# DiffVer.net
KiCad netlist of a schematic drawn in EAGLE
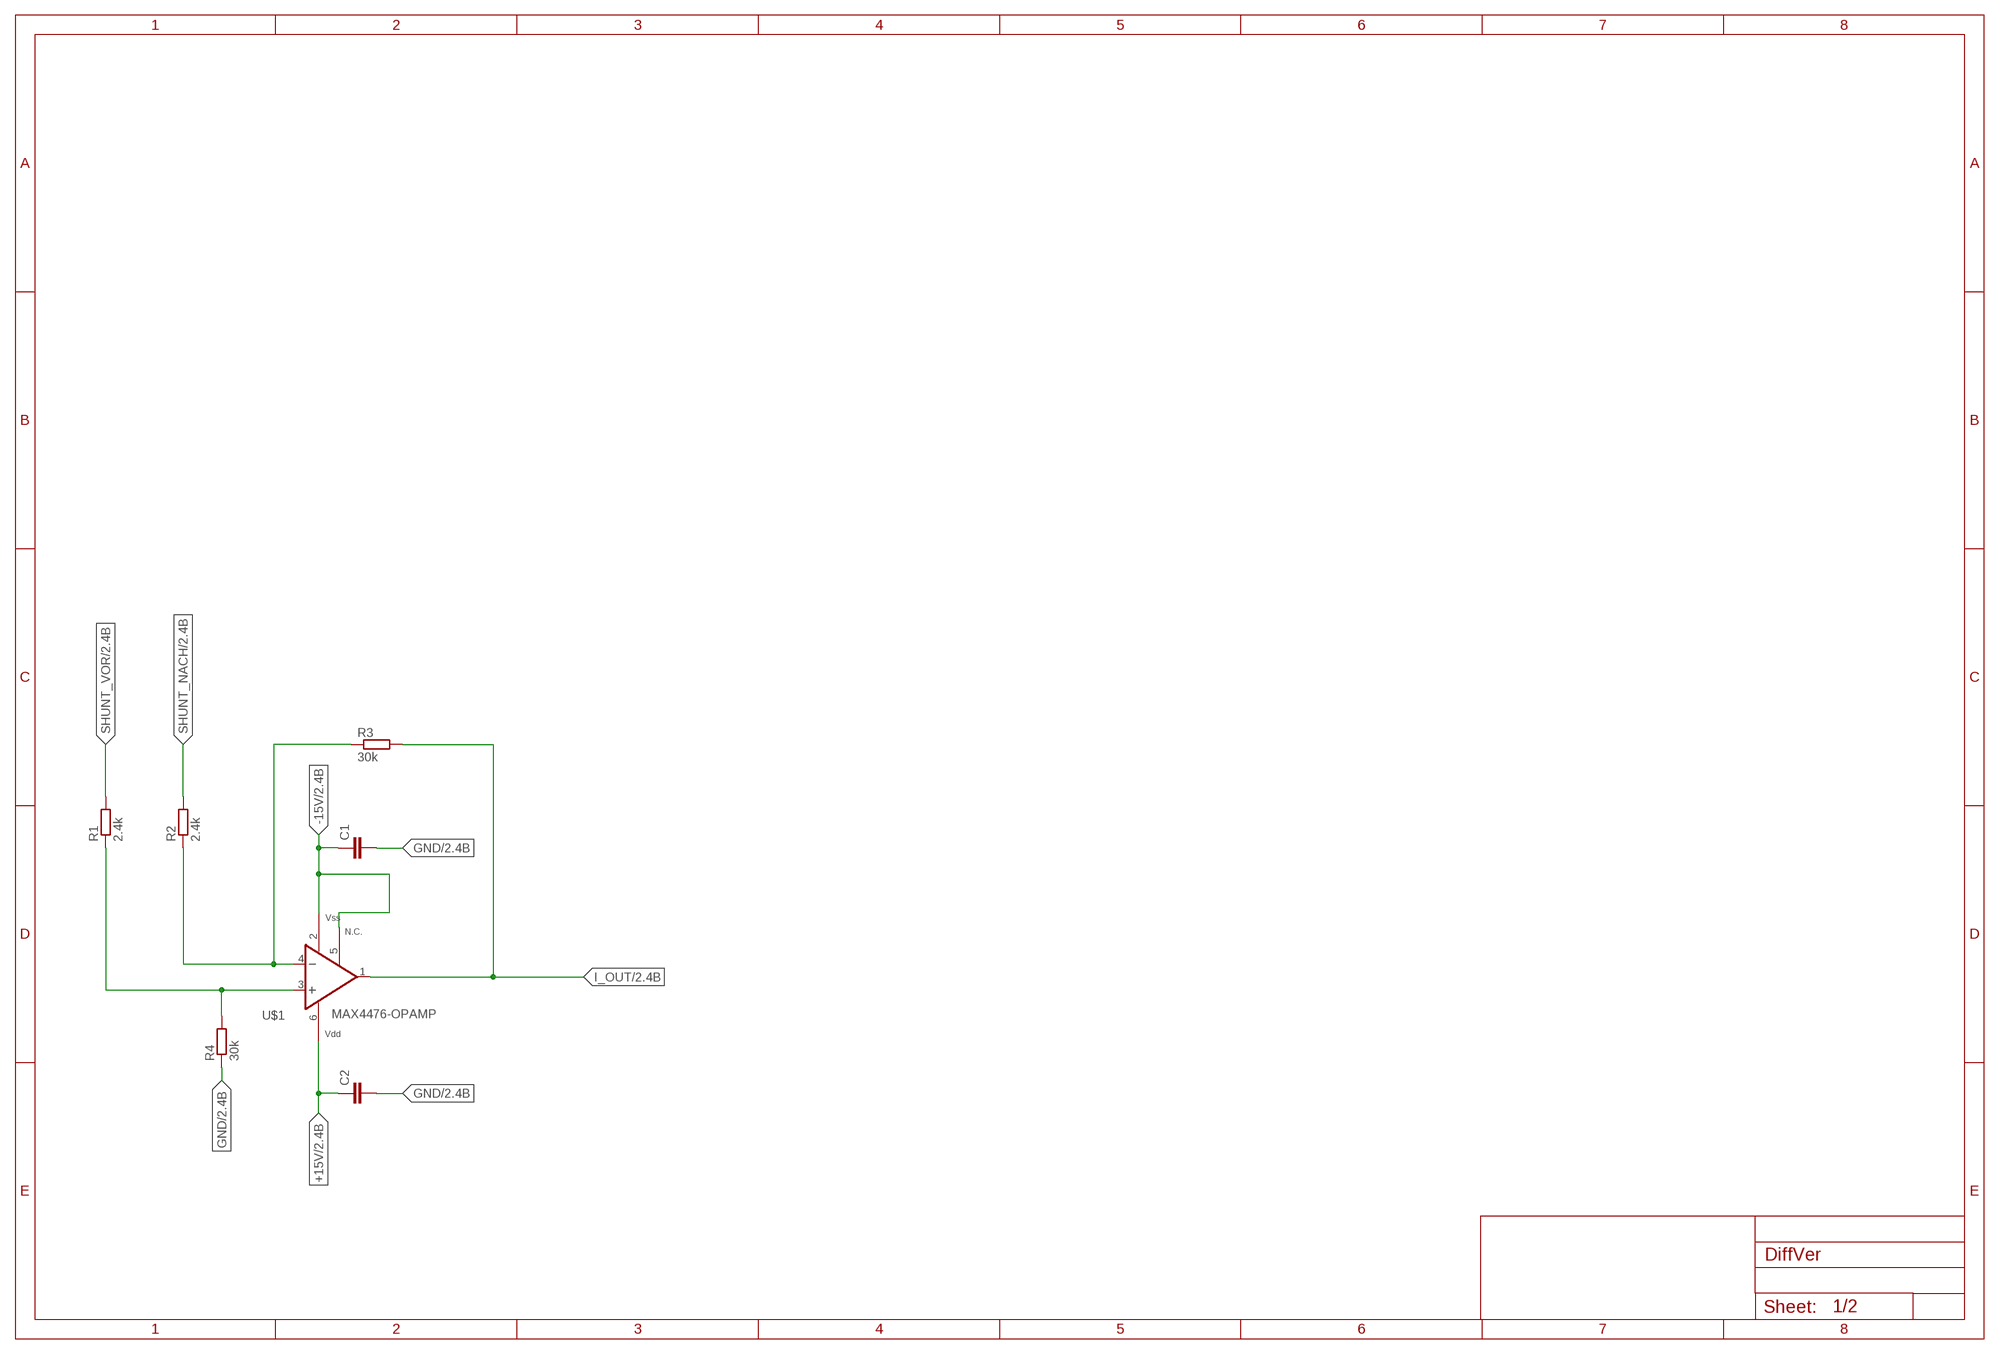
[diagram p0: schematic, sheet 1]
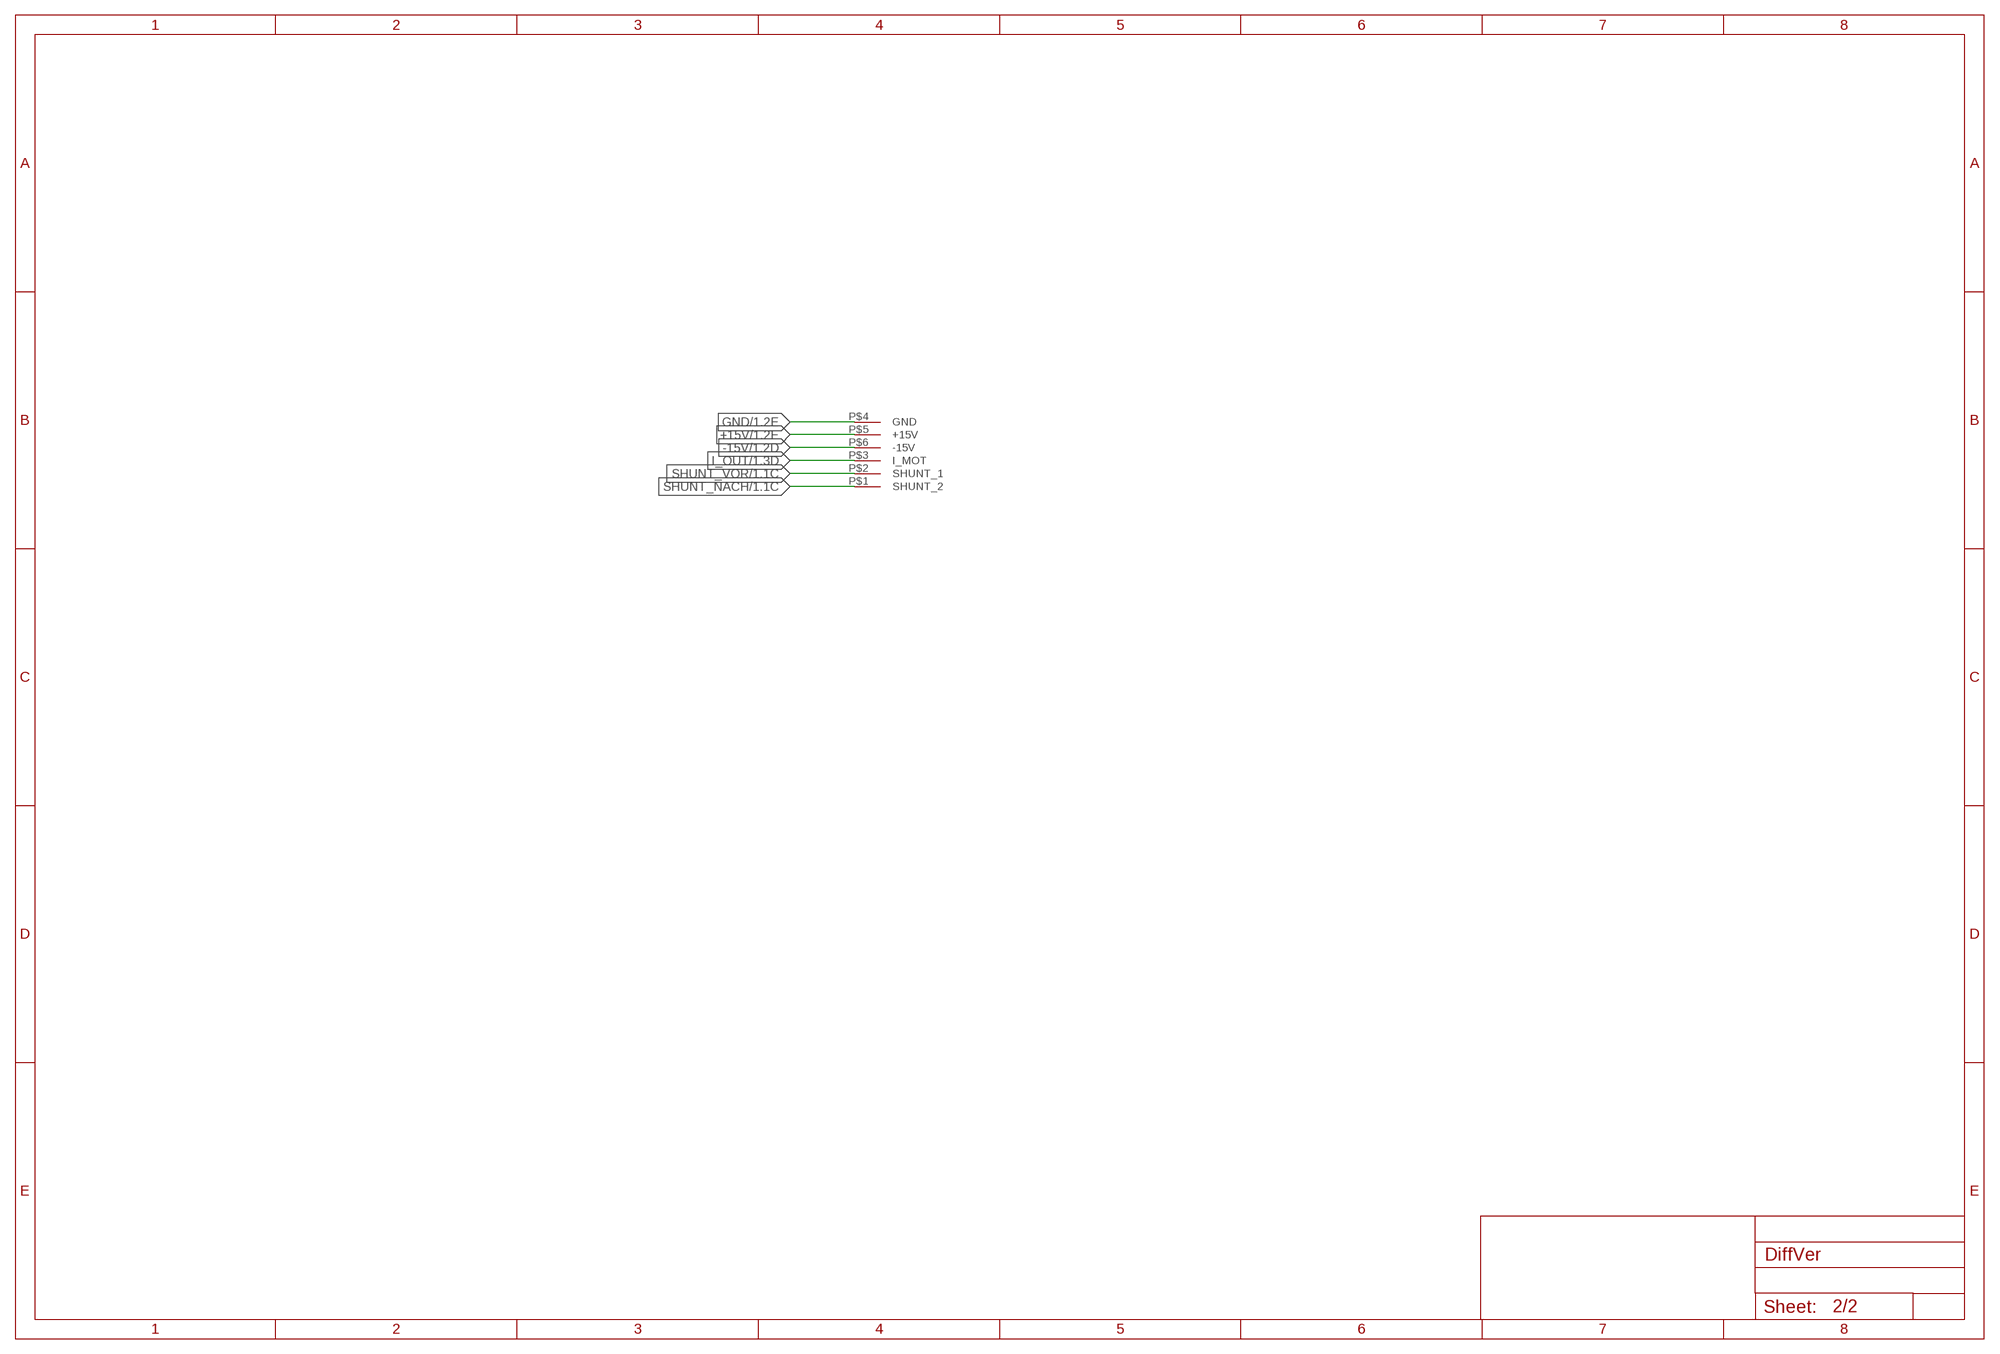
[diagram p1: schematic, sheet 2]

(export (version "E")
  (design (tool "Eeschema 10.0.6"))
  (components
    (comp (ref "U$2")
      (value "ADAPTERPLATINE_OPSHUNT")
      (footprint "eagle-import:ADAPTERPLATINE_OPSHUNT")
      (libsource (lib "eagle-import") (part "ADAPTERPLATINE_OPSHUNT"))
    )
    (comp (ref "C1")
      (value "C-EUC0805")
      (footprint "eagle-import:C0805")
      (libsource (lib "eagle-import") (part "C-EUC0805"))
    )
    (comp (ref "C2")
      (value "C-EUC0805")
      (footprint "eagle-import:C0805")
      (libsource (lib "eagle-import") (part "C-EUC0805"))
    )
    (comp (ref "R1")
      (value "2.4k")
      (footprint "eagle-import:R0805")
      (libsource (lib "eagle-import") (part "R-EU_R0805"))
    )
    (comp (ref "R2")
      (value "2.4k")
      (footprint "eagle-import:R0805")
      (libsource (lib "eagle-import") (part "R-EU_R0805"))
    )
    (comp (ref "R3")
      (value "30k")
      (footprint "eagle-import:R0805")
      (libsource (lib "eagle-import") (part "R-EU_R0805"))
    )
    (comp (ref "R4")
      (value "30k")
      (footprint "eagle-import:R0805")
      (libsource (lib "eagle-import") (part "R-EU_R0805"))
    )
    (comp (ref "U$1")
      (value "MAX4476-OPAMP")
      (footprint "eagle-import:SOT23-6")
      (libsource (lib "eagle-import") (part "MAX4476-OPAMP"))
    )
  )
  (nets
    (net (code "1") (name "+15V") (class "Default")
      (node (ref "C2") (pin "1") (pinfunction "1_1") (pintype "passive"))
      (node (ref "U$1") (pin "6") (pinfunction "VDD_6") (pintype "power_in"))
      (node (ref "U$2") (pin "P$5") (pinfunction "+15V_P$5") (pintype "bidirectional"))
    )
    (net (code "2") (name "-15V") (class "Default")
      (node (ref "C1") (pin "1") (pinfunction "1_1") (pintype "passive"))
      (node (ref "U$1") (pin "2") (pinfunction "VSS_2") (pintype "power_in"))
      (node (ref "U$1") (pin "5") (pinfunction "NC_5") (pintype "tri_state"))
      (node (ref "U$2") (pin "P$6") (pinfunction "-15V_P$6") (pintype "bidirectional"))
    )
    (net (code "3") (name "GND") (class "Default")
      (node (ref "C1") (pin "2") (pinfunction "2_2") (pintype "passive"))
      (node (ref "C2") (pin "2") (pinfunction "2_2") (pintype "passive"))
      (node (ref "R4") (pin "1") (pinfunction "1_1") (pintype "passive"))
      (node (ref "U$2") (pin "P$4") (pinfunction "GND_P$4") (pintype "bidirectional"))
    )
    (net (code "4") (name "I_OUT") (class "Default")
      (node (ref "R3") (pin "2") (pinfunction "2_2") (pintype "passive"))
      (node (ref "U$1") (pin "1") (pinfunction "OUT_1") (pintype "output"))
      (node (ref "U$2") (pin "P$3") (pinfunction "I_MOT_P$3") (pintype "bidirectional"))
    )
    (net (code "5") (name "Net-(U$1-+IN)") (class "Default")
      (node (ref "R1") (pin "1") (pinfunction "1_1") (pintype "passive"))
      (node (ref "R4") (pin "2") (pinfunction "2_2") (pintype "passive"))
      (node (ref "U$1") (pin "3") (pinfunction "+IN_3") (pintype "input"))
    )
    (net (code "6") (name "Net-(U$1--IN)") (class "Default")
      (node (ref "R2") (pin "1") (pinfunction "1_1") (pintype "passive"))
      (node (ref "R3") (pin "1") (pinfunction "1_1") (pintype "passive"))
      (node (ref "U$1") (pin "4") (pinfunction "-IN_4") (pintype "input"))
    )
    (net (code "7") (name "SHUNT_NACH") (class "Default")
      (node (ref "R2") (pin "2") (pinfunction "2_2") (pintype "passive"))
      (node (ref "U$2") (pin "P$1") (pinfunction "SHUNT_2_P$1") (pintype "bidirectional"))
    )
    (net (code "8") (name "SHUNT_VOR") (class "Default")
      (node (ref "R1") (pin "2") (pinfunction "2_2") (pintype "passive"))
      (node (ref "U$2") (pin "P$2") (pinfunction "SHUNT_1_P$2") (pintype "bidirectional"))
    )
  )
)
